# Front_panel.net
KiCad netlist of a schematic drawn in Altium Designer
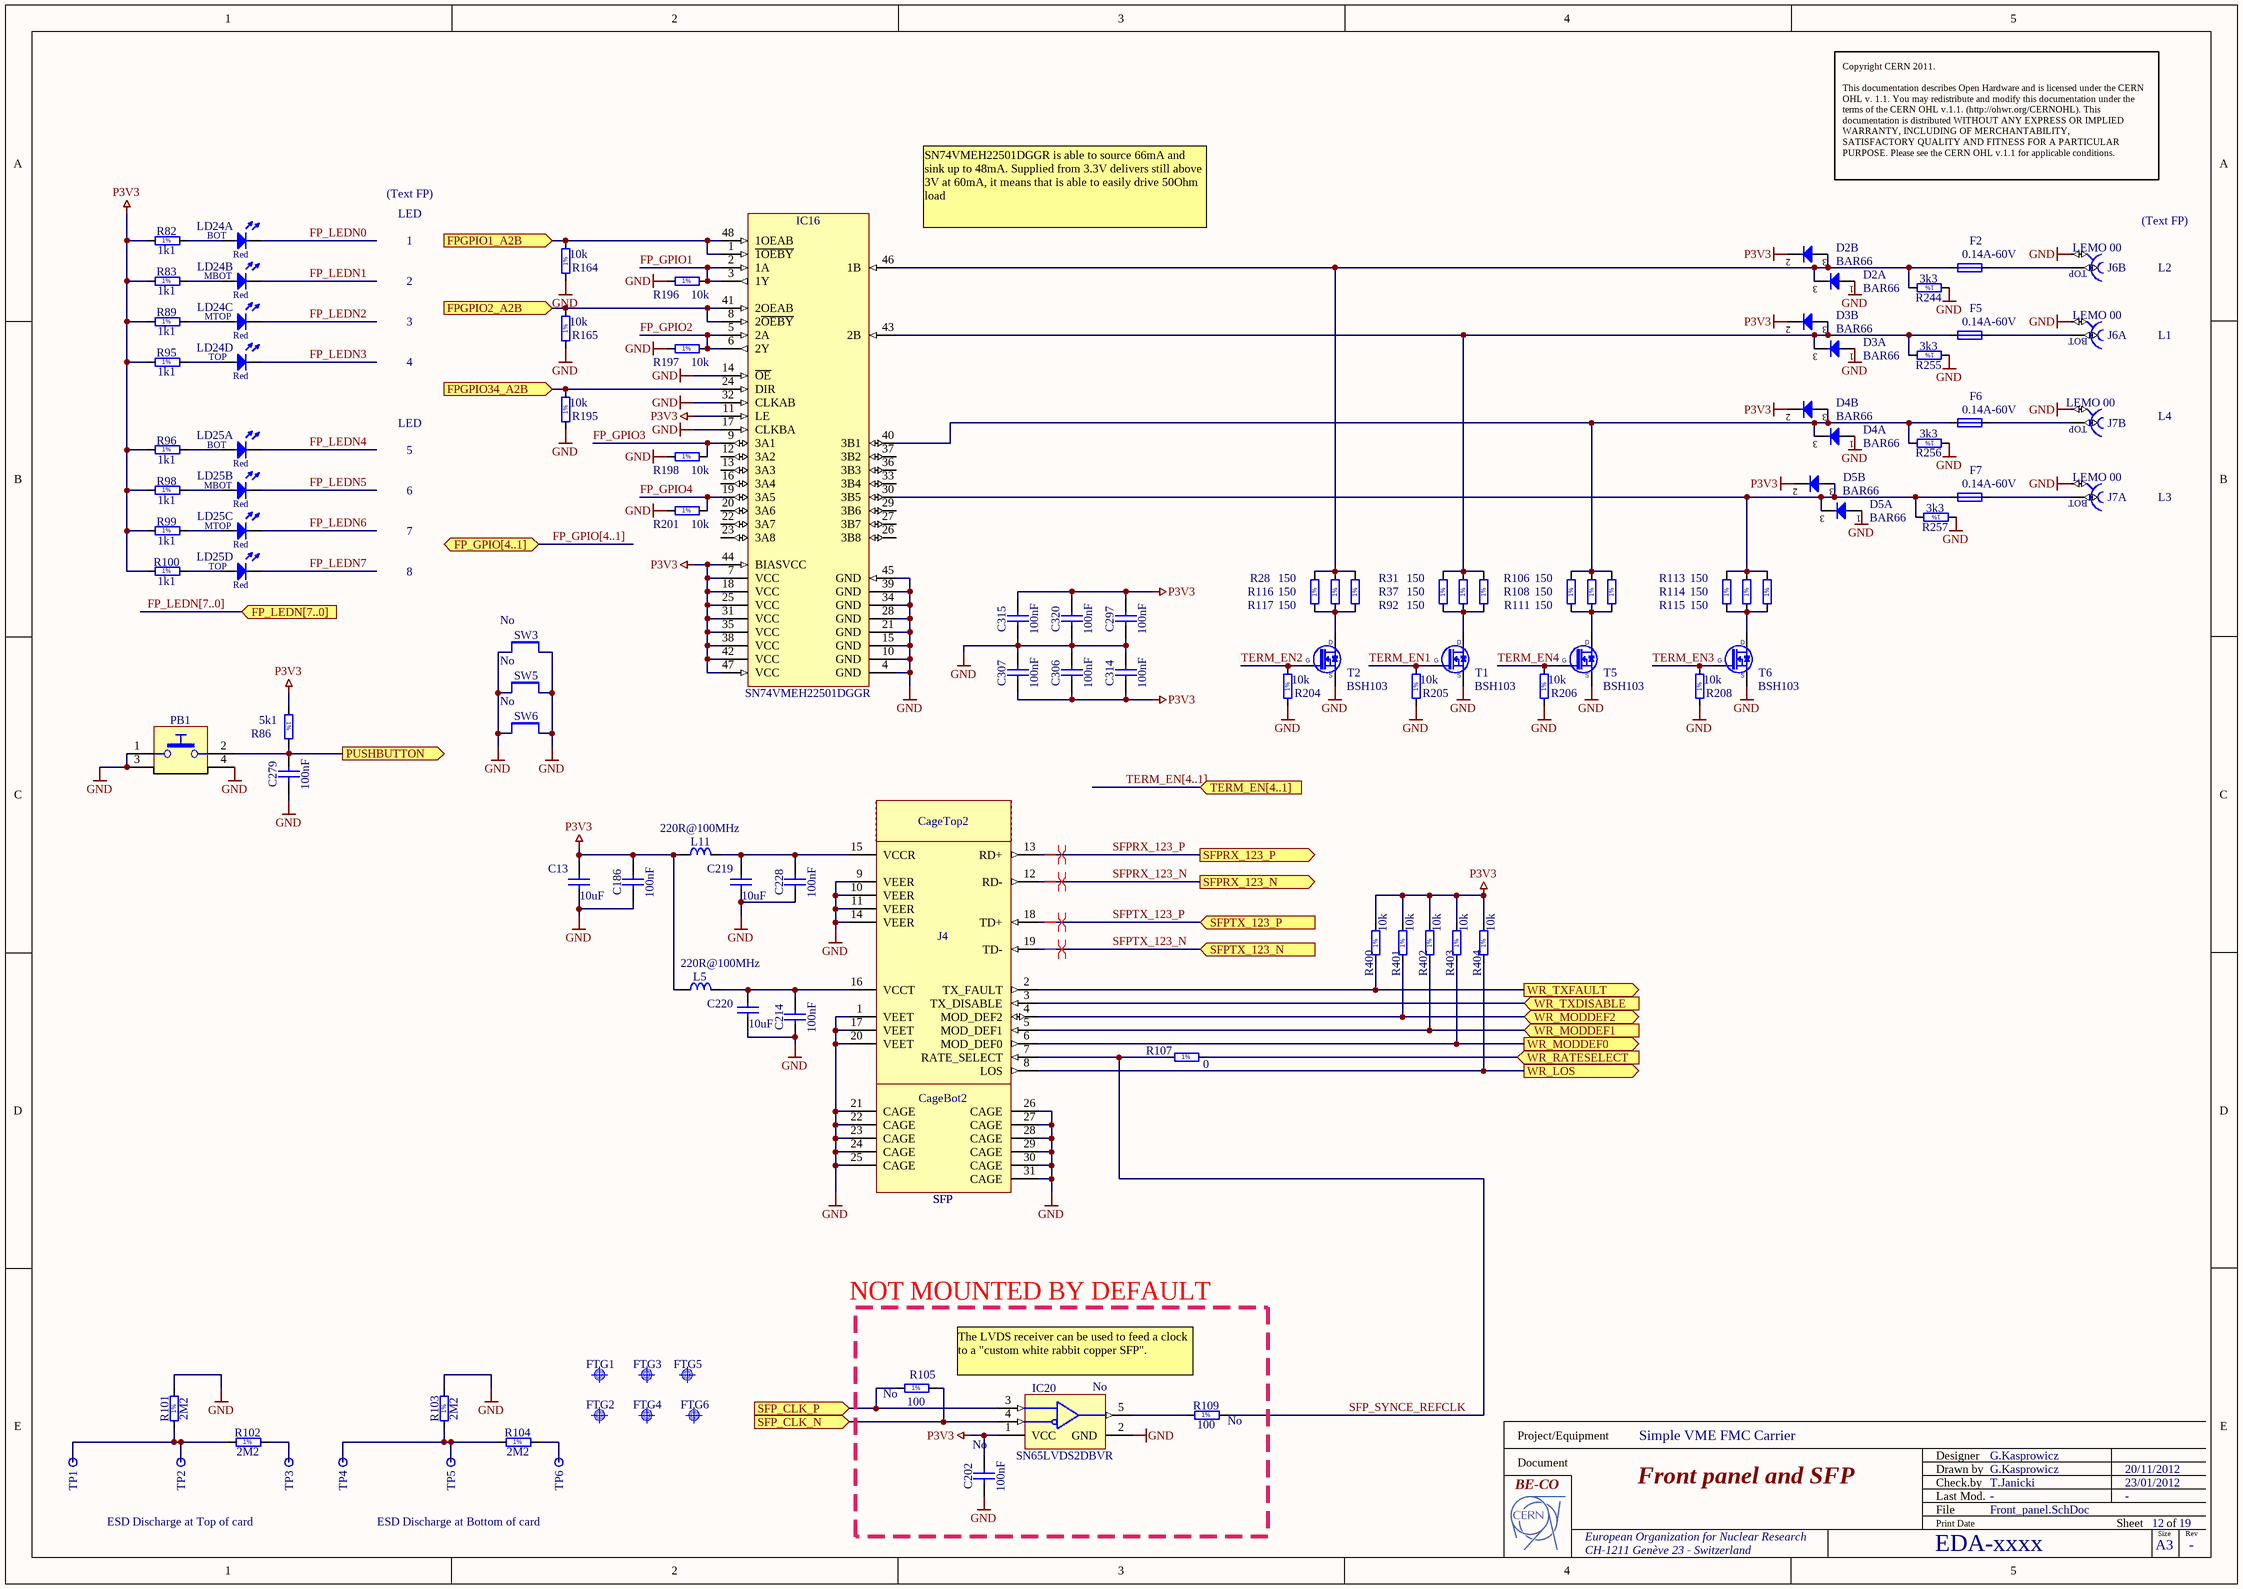
[diagram p0: Front_panel.SchDoc]

(export (version "E")
  (design (tool "Eeschema 10.0.6"))
  (components
    (comp (ref "C13")
      (value "10uF")
      (footprint "CAPC3225X270N")
      (description "Non-polarised capacitor")
      (fields (field (name "PART NUMBER") "CC1210_10UF_25V_10%_X7R") (field (name "VOLTAGE") "25V"))
      (libsource (lib "Capacitors") (part "Capacitor - non polarized"))
    )
    (comp (ref "C186")
      (value "100nF")
      (footprint "CAPC1005X55N")
      (description "Non-polarised capacitor")
      (fields (field (name "PART NUMBER") "CC0402_100NF_16V_10%_X7R") (field (name "VOLTAGE") "16V"))
      (libsource (lib "Capacitors") (part "Capacitor - non polarized"))
    )
    (comp (ref "C202")
      (value "100nF")
      (footprint "CAPC1005X55N")
      (description "Non-polarised capacitor")
      (fields
        (field (name "PART NUMBER") "CC0402_100NF_16V_10%_X7R")
        (field (name "VOLTAGE") "16V")
        (field (name "MOUNTED") "No")
      )
      (libsource (lib "Capacitors") (part "Capacitor - non polarized"))
    )
    (comp (ref "C214")
      (value "100nF")
      (footprint "CAPC1005X55N")
      (description "Non-polarised capacitor")
      (fields (field (name "PART NUMBER") "CC0402_100NF_16V_10%_X7R") (field (name "VOLTAGE") "16V"))
      (libsource (lib "Capacitors") (part "Capacitor - non polarized"))
    )
    (comp (ref "C219")
      (value "10uF")
      (footprint "CAPC3225X270N")
      (description "Non-polarised capacitor")
      (fields (field (name "PART NUMBER") "CC1210_10UF_25V_10%_X7R") (field (name "VOLTAGE") "25V"))
      (libsource (lib "Capacitors") (part "Capacitor - non polarized"))
    )
    (comp (ref "C220")
      (value "10uF")
      (footprint "CAPC3225X270N")
      (description "Non-polarised capacitor")
      (fields (field (name "PART NUMBER") "CC1210_10UF_25V_10%_X7R") (field (name "VOLTAGE") "25V"))
      (libsource (lib "Capacitors") (part "Capacitor - non polarized"))
    )
    (comp (ref "C228")
      (value "100nF")
      (footprint "CAPC1005X55N")
      (description "Non-polarised capacitor")
      (fields (field (name "PART NUMBER") "CC0402_100NF_16V_10%_X7R") (field (name "VOLTAGE") "16V"))
      (libsource (lib "Capacitors") (part "Capacitor - non polarized"))
    )
    (comp (ref "C279")
      (value "100nF")
      (footprint "CAPC1005X55N")
      (description "Non-polarised capacitor")
      (fields (field (name "PART NUMBER") "CC0402_100NF_16V_10%_X7R") (field (name "VOLTAGE") "16V"))
      (libsource (lib "Capacitors") (part "Capacitor - non polarized"))
    )
    (comp (ref "C297")
      (value "100nF")
      (footprint "CAPC1005X55N")
      (description "Non-polarised capacitor")
      (fields (field (name "PART NUMBER") "CC0402_100NF_16V_10%_X7R") (field (name "VOLTAGE") "16V"))
      (libsource (lib "Capacitors") (part "Capacitor - non polarized"))
    )
    (comp (ref "C306")
      (value "100nF")
      (footprint "CAPC1005X55N")
      (description "Non-polarised capacitor")
      (fields (field (name "PART NUMBER") "CC0402_100NF_16V_10%_X7R") (field (name "VOLTAGE") "16V"))
      (libsource (lib "Capacitors") (part "Capacitor - non polarized"))
    )
    (comp (ref "C307")
      (value "100nF")
      (footprint "CAPC1005X55N")
      (description "Non-polarised capacitor")
      (fields (field (name "PART NUMBER") "CC0402_100NF_16V_10%_X7R") (field (name "VOLTAGE") "16V"))
      (libsource (lib "Capacitors") (part "Capacitor - non polarized"))
    )
    (comp (ref "C314")
      (value "100nF")
      (footprint "CAPC1005X55N")
      (description "Non-polarised capacitor")
      (fields (field (name "PART NUMBER") "CC0402_100NF_16V_10%_X7R") (field (name "VOLTAGE") "16V"))
      (libsource (lib "Capacitors") (part "Capacitor - non polarized"))
    )
    (comp (ref "C315")
      (value "100nF")
      (footprint "CAPC1005X55N")
      (description "Non-polarised capacitor")
      (fields (field (name "PART NUMBER") "CC0402_100NF_16V_10%_X7R") (field (name "VOLTAGE") "16V"))
      (libsource (lib "Capacitors") (part "Capacitor - non polarized"))
    )
    (comp (ref "C320")
      (value "100nF")
      (footprint "CAPC1005X55N")
      (description "Non-polarised capacitor")
      (fields (field (name "PART NUMBER") "CC0402_100NF_16V_10%_X7R") (field (name "VOLTAGE") "16V"))
      (libsource (lib "Capacitors") (part "Capacitor - non polarized"))
    )
    (comp (ref "CageBot2")
      (value "SFP")
      (footprint "TYCO_6367034-1")
      (description "SFP  Cage Bottom (Small Form-factor Pluggable)")
      (fields (field (name "PART NUMBER") "TYCO_6367034-1") (field (name "MANUFACTURER") "TYCO ELECTRONICS"))
      (libsource (lib "Connectors") (part "SFPx1_Cage Bottom"))
    )
    (comp (ref "CageTop2")
      (value "SFP")
      (footprint "TYCO_6367035-1")
      (description "SFP  Cage Top (Small Form-factor Pluggable)")
      (fields (field (name "PART NUMBER") "TYCO_6367035-1") (field (name "MANUFACTURER") "TYCO ELECTRONICS"))
      (libsource (lib "Connectors") (part "SFPx1_Cage Top"))
    )
    (comp (ref "D2")
      (value "BAR66")
      (footprint "SOT95P240X110-3N")
      (description "Serial Diode")
      (fields (field (name "VOLTAGE") "150V") (field (name "POWER") "250mA"))
      (libsource (lib "ICs And Semiconductors") (part "Diode x2 A1C3_A3C2"))
    )
    (comp (ref "D3")
      (value "BAR66")
      (footprint "SOT95P240X110-3N")
      (description "Serial Diode")
      (fields (field (name "VOLTAGE") "150V") (field (name "POWER") "250mA"))
      (libsource (lib "ICs And Semiconductors") (part "Diode x2 A1C3_A3C2"))
    )
    (comp (ref "D4")
      (value "BAR66")
      (footprint "SOT95P240X110-3N")
      (description "Serial Diode")
      (fields (field (name "VOLTAGE") "150V") (field (name "POWER") "250mA"))
      (libsource (lib "ICs And Semiconductors") (part "Diode x2 A1C3_A3C2"))
    )
    (comp (ref "D5")
      (value "BAR66")
      (footprint "SOT95P240X110-3N")
      (description "Serial Diode")
      (fields (field (name "VOLTAGE") "150V") (field (name "POWER") "250mA"))
      (libsource (lib "ICs And Semiconductors") (part "Diode x2 A1C3_A3C2"))
    )
    (comp (ref "F2")
      (value "0.14A-60V")
      (footprint "FUSRC4632X90N")
      (description "Fuse")
      (fields
        (field (name "PART NUMBER") "FUSR1812_TYCO-miniSMD0114F")
        (field (name "MANUFACTURER") "TYCO ELECTRONICS")
      )
      (libsource (lib "Eletro-mechanical") (part "Fuse"))
    )
    (comp (ref "F5")
      (value "0.14A-60V")
      (footprint "FUSRC4632X90N")
      (description "Fuse")
      (fields
        (field (name "PART NUMBER") "FUSR1812_TYCO-miniSMD0114F")
        (field (name "MANUFACTURER") "TYCO ELECTRONICS")
      )
      (libsource (lib "Eletro-mechanical") (part "Fuse"))
    )
    (comp (ref "F6")
      (value "0.14A-60V")
      (footprint "FUSRC4632X90N")
      (description "Fuse")
      (fields
        (field (name "PART NUMBER") "FUSR1812_TYCO-miniSMD0114F")
        (field (name "MANUFACTURER") "TYCO ELECTRONICS")
      )
      (libsource (lib "Eletro-mechanical") (part "Fuse"))
    )
    (comp (ref "F7")
      (value "0.14A-60V")
      (footprint "FUSRC4632X90N")
      (description "Fuse")
      (fields
        (field (name "PART NUMBER") "FUSR1812_TYCO-miniSMD0114F")
        (field (name "MANUFACTURER") "TYCO ELECTRONICS")
      )
      (libsource (lib "Eletro-mechanical") (part "Fuse"))
    )
    (comp (ref "FTG1")
      (value "Use only in PCB")
      (footprint "FIDUCIAL_TOP_S100-200")
      (description "Fiducial Target")
      (fields (field (name "PART NUMBER") "FIDUCIAL_TARGET_S100-200"))
      (libsource (lib "Eletro-mechanical") (part "Fiducial Target"))
    )
    (comp (ref "FTG2")
      (value "Use only in PCB")
      (footprint "FIDUCIAL_TOP_S100-200")
      (description "Fiducial Target")
      (fields (field (name "PART NUMBER") "FIDUCIAL_TARGET_S100-200"))
      (libsource (lib "Eletro-mechanical") (part "Fiducial Target"))
    )
    (comp (ref "FTG3")
      (value "Use only in PCB")
      (footprint "FIDUCIAL_TOP_S100-200")
      (description "Fiducial Target")
      (fields (field (name "PART NUMBER") "FIDUCIAL_TARGET_S100-200"))
      (libsource (lib "Eletro-mechanical") (part "Fiducial Target"))
    )
    (comp (ref "FTG4")
      (value "Use only in PCB")
      (footprint "FIDUCIAL_TOP_S100-200")
      (description "Fiducial Target")
      (fields (field (name "PART NUMBER") "FIDUCIAL_TARGET_S100-200"))
      (libsource (lib "Eletro-mechanical") (part "Fiducial Target"))
    )
    (comp (ref "FTG5")
      (value "Use only in PCB")
      (footprint "FIDUCIAL_TOP_S100-200")
      (description "Fiducial Target")
      (fields (field (name "PART NUMBER") "FIDUCIAL_TARGET_S100-200"))
      (libsource (lib "Eletro-mechanical") (part "Fiducial Target"))
    )
    (comp (ref "FTG6")
      (value "Use only in PCB")
      (footprint "FIDUCIAL_TOP_S100-200")
      (description "Fiducial Target")
      (fields (field (name "PART NUMBER") "FIDUCIAL_TARGET_S100-200"))
      (libsource (lib "Eletro-mechanical") (part "Fiducial Target"))
    )
    (comp (ref "IC16")
      (value "SN74VMEH22501DGGR")
      (footprint "SOP50P810X120-48N")
      (description "8-Bit Universal Bus Transceiver and Two 1-Bit Bus Transceivers with 3-State Outputs")
      (fields (field (name "MANUFACTURER") "TEXAS INSTRUMENTS"))
      (libsource (lib "ICs And Semiconductors") (part "74VMEH22501"))
    )
    (comp (ref "IC20")
      (value "SN65LVDS2DBVR")
      (footprint "SOT95P280X145-5N")
      (description "High-Speed Differential Line Receiver")
      (fields (field (name "MANUFACTURER") "TEXAS INSTRUMENTS") (field (name "MOUNTED") "No"))
      (libsource (lib "ICs And Semiconductors") (part "SN65LVDS2DBVR"))
    )
    (comp (ref "J4")
      (value "SFP")
      (footprint "TYCO_1367073-1")
      (description "20 Position SFP  Connector (Small Form-factor Pluggable)")
      (fields (field (name "PART NUMBER") "TYCO_1367073-1") (field (name "MANUFACTURER") "TYCO ELECTRONICS"))
      (libsource (lib "Connectors") (part "SFPx1"))
    )
    (comp (ref "J6")
      (value "LEMO 00")
      (footprint "LEMO_EPY.00.250.NTNY")
      (description "Dual Female Coax 1-2 Common Shield 3")
      (fields (field (name "PART NUMBER") "LEMO_EPY.00.250.NTNY") (field (name "MANUFACTURER") "LEMO"))
      (libsource (lib "Connectors") (part "LEMO_EPY.00.250.NTN"))
    )
    (comp (ref "J7")
      (value "LEMO 00")
      (footprint "LEMO_EPY.00.250.NTNY")
      (description "Dual Female Coax 1-2 Common Shield 3")
      (fields (field (name "PART NUMBER") "LEMO_EPY.00.250.NTNY") (field (name "MANUFACTURER") "LEMO"))
      (libsource (lib "Connectors") (part "LEMO_EPY.00.250.NTN"))
    )
    (comp (ref "L5")
      (value "220R@100MHz")
      (footprint "INDC2012X105N")
      (description "Inductor")
      (fields (field (name "PART NUMBER") "IND0805_MURATA_BLM21PG221SN1D") (field (name "POWER") "2A"))
      (libsource (lib "Inductors & Transformers") (part "Inductor"))
    )
    (comp (ref "L11")
      (value "220R@100MHz")
      (footprint "INDC2012X105N")
      (description "Inductor")
      (fields (field (name "PART NUMBER") "IND0805_MURATA_BLM21PG221SN1D") (field (name "POWER") "2A"))
      (libsource (lib "Inductors & Transformers") (part "Inductor"))
    )
    (comp (ref "LD24")
      (value "HE Red")
      (footprint "LED_BIVAR_H485CHDL")
      (description "LED x4 Red 1C2A-BOT_3C4A_5C6A_7C8A-TOP")
      (fields (field (name "PART NUMBER") "LED_BIVAR_H485CHDL") (field (name "MANUFACTURER") "BIVAR"))
      (libsource (lib "ICs And Semiconductors") (part "LED x4 Red 1C2A-BOT_3C4A_5C6A_7C8A-TOP"))
    )
    (comp (ref "LD25")
      (value "HE Red")
      (footprint "LED_BIVAR_H485CHDL")
      (description "LED x4 Red 1C2A-BOT_3C4A_5C6A_7C8A-TOP")
      (fields (field (name "PART NUMBER") "LED_BIVAR_H485CHDL") (field (name "MANUFACTURER") "BIVAR"))
      (libsource (lib "ICs And Semiconductors") (part "LED x4 Red 1C2A-BOT_3C4A_5C6A_7C8A-TOP"))
    )
    (comp (ref "PB1")
      (value "Push Button")
      (footprint "PB_ALPS_SKHHLQA010")
      (description "Push-Button Switch SPDT")
      (fields (field (name "PART NUMBER") "PB_ALPS_SKHHLQA010") (field (name "MANUFACTURER") "ALPS"))
      (libsource (lib "Eletro-mechanical") (part "PB SPST 1NO-2NO 34CASE"))
    )
    (comp (ref "R28")
      (value "150")
      (footprint "RESC3216X65N")
      (description "Resistor - 1%")
      (fields (field (name "PART NUMBER") "R1206_150R_1%_0.25W_100PPM") (field (name "POWER") "0.25W"))
      (libsource (lib "Resistors") (part "Resistor - 1%"))
    )
    (comp (ref "R31")
      (value "150")
      (footprint "RESC3216X65N")
      (description "Resistor - 1%")
      (fields (field (name "PART NUMBER") "R1206_150R_1%_0.25W_100PPM") (field (name "POWER") "0.25W"))
      (libsource (lib "Resistors") (part "Resistor - 1%"))
    )
    (comp (ref "R37")
      (value "150")
      (footprint "RESC3216X65N")
      (description "Resistor - 1%")
      (fields (field (name "PART NUMBER") "R1206_150R_1%_0.25W_100PPM") (field (name "POWER") "0.25W"))
      (libsource (lib "Resistors") (part "Resistor - 1%"))
    )
    (comp (ref "R82")
      (value "1k1")
      (footprint "RESC1608X55N")
      (description "Resistor - 1%")
      (fields (field (name "PART NUMBER") "R0603_1K1_1%_0.1W_100PPM") (field (name "POWER") "0.1W"))
      (libsource (lib "Resistors") (part "Resistor - 1%"))
    )
    (comp (ref "R83")
      (value "1k1")
      (footprint "RESC1608X55N")
      (description "Resistor - 1%")
      (fields (field (name "PART NUMBER") "R0603_1K1_1%_0.1W_100PPM") (field (name "POWER") "0.1W"))
      (libsource (lib "Resistors") (part "Resistor - 1%"))
    )
    (comp (ref "R86")
      (value "5k1")
      (footprint "RESC1608X55N")
      (description "Resistor - 1%")
      (fields (field (name "PART NUMBER") "R0603_5K1_1%_0.1W_100PPM") (field (name "POWER") "0.1W"))
      (libsource (lib "Resistors") (part "Resistor - 1%"))
    )
    (comp (ref "R89")
      (value "1k1")
      (footprint "RESC1608X55N")
      (description "Resistor - 1%")
      (fields (field (name "PART NUMBER") "R0603_1K1_1%_0.1W_100PPM") (field (name "POWER") "0.1W"))
      (libsource (lib "Resistors") (part "Resistor - 1%"))
    )
    (comp (ref "R92")
      (value "150")
      (footprint "RESC3216X65N")
      (description "Resistor - 1%")
      (fields (field (name "PART NUMBER") "R1206_150R_1%_0.25W_100PPM") (field (name "POWER") "0.25W"))
      (libsource (lib "Resistors") (part "Resistor - 1%"))
    )
    (comp (ref "R95")
      (value "1k1")
      (footprint "RESC1608X55N")
      (description "Resistor - 1%")
      (fields (field (name "PART NUMBER") "R0603_1K1_1%_0.1W_100PPM") (field (name "POWER") "0.1W"))
      (libsource (lib "Resistors") (part "Resistor - 1%"))
    )
    (comp (ref "R96")
      (value "1k1")
      (footprint "RESC1608X55N")
      (description "Resistor - 1%")
      (fields (field (name "PART NUMBER") "R0603_1K1_1%_0.1W_100PPM") (field (name "POWER") "0.1W"))
      (libsource (lib "Resistors") (part "Resistor - 1%"))
    )
    (comp (ref "R98")
      (value "1k1")
      (footprint "RESC1608X55N")
      (description "Resistor - 1%")
      (fields (field (name "PART NUMBER") "R0603_1K1_1%_0.1W_100PPM") (field (name "POWER") "0.1W"))
      (libsource (lib "Resistors") (part "Resistor - 1%"))
    )
    (comp (ref "R99")
      (value "1k1")
      (footprint "RESC1608X55N")
      (description "Resistor - 1%")
      (fields (field (name "PART NUMBER") "R0603_1K1_1%_0.1W_100PPM") (field (name "POWER") "0.1W"))
      (libsource (lib "Resistors") (part "Resistor - 1%"))
    )
    (comp (ref "R100")
      (value "1k1")
      (footprint "RESC1608X55N")
      (description "Resistor - 1%")
      (fields (field (name "PART NUMBER") "R0603_1K1_1%_0.1W_100PPM") (field (name "POWER") "0.1W"))
      (libsource (lib "Resistors") (part "Resistor - 1%"))
    )
    (comp (ref "R101")
      (value "2M2")
      (footprint "RESC2012X60N")
      (description "Resistor - 1%")
      (fields (field (name "PART NUMBER") "R0805_2M2_1%_0.125W_100PPM") (field (name "POWER") "0.125W"))
      (libsource (lib "Resistors") (part "Resistor - 1%"))
    )
    (comp (ref "R102")
      (value "2M2")
      (footprint "RESC2012X60N")
      (description "Resistor - 1%")
      (fields (field (name "PART NUMBER") "R0805_2M2_1%_0.125W_100PPM") (field (name "POWER") "0.125W"))
      (libsource (lib "Resistors") (part "Resistor - 1%"))
    )
    (comp (ref "R103")
      (value "2M2")
      (footprint "RESC2012X60N")
      (description "Resistor - 1%")
      (fields (field (name "PART NUMBER") "R0805_2M2_1%_0.125W_100PPM") (field (name "POWER") "0.125W"))
      (libsource (lib "Resistors") (part "Resistor - 1%"))
    )
    (comp (ref "R104")
      (value "2M2")
      (footprint "RESC2012X60N")
      (description "Resistor - 1%")
      (fields (field (name "PART NUMBER") "R0805_2M2_1%_0.125W_100PPM") (field (name "POWER") "0.125W"))
      (libsource (lib "Resistors") (part "Resistor - 1%"))
    )
    (comp (ref "R105")
      (value "100")
      (footprint "RESC1608X55N")
      (description "Resistor - 1%")
      (fields
        (field (name "PART NUMBER") "R0603_100R_1%_0.1W_100PPM")
        (field (name "POWER") "0.1W")
        (field (name "MOUNTED") "No")
      )
      (libsource (lib "Resistors") (part "Resistor - 1%"))
    )
    (comp (ref "R106")
      (value "150")
      (footprint "RESC3216X65N")
      (description "Resistor - 1%")
      (fields (field (name "PART NUMBER") "R1206_150R_1%_0.25W_100PPM") (field (name "POWER") "0.25W"))
      (libsource (lib "Resistors") (part "Resistor - 1%"))
    )
    (comp (ref "R107")
      (value "0")
      (footprint "RESC1608X55N")
      (description "Resistor - 1%")
      (fields (field (name "PART NUMBER") "R0603_0R_JUMPER") (field (name "MANUFACTURER") "GENERIC"))
      (libsource (lib "Resistors") (part "Resistor - 1%"))
    )
    (comp (ref "R108")
      (value "150")
      (footprint "RESC3216X65N")
      (description "Resistor - 1%")
      (fields (field (name "PART NUMBER") "R1206_150R_1%_0.25W_100PPM") (field (name "POWER") "0.25W"))
      (libsource (lib "Resistors") (part "Resistor - 1%"))
    )
    (comp (ref "R109")
      (value "100")
      (footprint "RESC1608X55N")
      (description "Resistor - 1%")
      (fields
        (field (name "PART NUMBER") "R0603_100R_1%_0.1W_100PPM")
        (field (name "POWER") "0.1W")
        (field (name "MOUNTED") "No")
      )
      (libsource (lib "Resistors") (part "Resistor - 1%"))
    )
    (comp (ref "R111")
      (value "150")
      (footprint "RESC3216X65N")
      (description "Resistor - 1%")
      (fields (field (name "PART NUMBER") "R1206_150R_1%_0.25W_100PPM") (field (name "POWER") "0.25W"))
      (libsource (lib "Resistors") (part "Resistor - 1%"))
    )
    (comp (ref "R113")
      (value "150")
      (footprint "RESC3216X65N")
      (description "Resistor - 1%")
      (fields (field (name "PART NUMBER") "R1206_150R_1%_0.25W_100PPM") (field (name "POWER") "0.25W"))
      (libsource (lib "Resistors") (part "Resistor - 1%"))
    )
    (comp (ref "R114")
      (value "150")
      (footprint "RESC3216X65N")
      (description "Resistor - 1%")
      (fields (field (name "PART NUMBER") "R1206_150R_1%_0.25W_100PPM") (field (name "POWER") "0.25W"))
      (libsource (lib "Resistors") (part "Resistor - 1%"))
    )
    (comp (ref "R115")
      (value "150")
      (footprint "RESC3216X65N")
      (description "Resistor - 1%")
      (fields (field (name "PART NUMBER") "R1206_150R_1%_0.25W_100PPM") (field (name "POWER") "0.25W"))
      (libsource (lib "Resistors") (part "Resistor - 1%"))
    )
    (comp (ref "R116")
      (value "150")
      (footprint "RESC3216X65N")
      (description "Resistor - 1%")
      (fields (field (name "PART NUMBER") "R1206_150R_1%_0.25W_100PPM") (field (name "POWER") "0.25W"))
      (libsource (lib "Resistors") (part "Resistor - 1%"))
    )
    (comp (ref "R117")
      (value "150")
      (footprint "RESC3216X65N")
      (description "Resistor - 1%")
      (fields (field (name "PART NUMBER") "R1206_150R_1%_0.25W_100PPM") (field (name "POWER") "0.25W"))
      (libsource (lib "Resistors") (part "Resistor - 1%"))
    )
    (comp (ref "R164")
      (value "10k")
      (footprint "RESC1608X55N")
      (description "Resistor - 1%")
      (fields (field (name "PART NUMBER") "R0603_10K_1%_0.1W_100PPM") (field (name "POWER") "0.1W"))
      (libsource (lib "Resistors") (part "Resistor - 1%"))
    )
    (comp (ref "R165")
      (value "10k")
      (footprint "RESC1608X55N")
      (description "Resistor - 1%")
      (fields (field (name "PART NUMBER") "R0603_10K_1%_0.1W_100PPM") (field (name "POWER") "0.1W"))
      (libsource (lib "Resistors") (part "Resistor - 1%"))
    )
    (comp (ref "R195")
      (value "10k")
      (footprint "RESC1608X55N")
      (description "Resistor - 1%")
      (fields (field (name "PART NUMBER") "R0603_10K_1%_0.1W_100PPM") (field (name "POWER") "0.1W"))
      (libsource (lib "Resistors") (part "Resistor - 1%"))
    )
    (comp (ref "R196")
      (value "10k")
      (footprint "RESC1608X55N")
      (description "Resistor - 1%")
      (fields (field (name "PART NUMBER") "R0603_10K_1%_0.1W_100PPM") (field (name "POWER") "0.1W"))
      (libsource (lib "Resistors") (part "Resistor - 1%"))
    )
    (comp (ref "R197")
      (value "10k")
      (footprint "RESC1608X55N")
      (description "Resistor - 1%")
      (fields (field (name "PART NUMBER") "R0603_10K_1%_0.1W_100PPM") (field (name "POWER") "0.1W"))
      (libsource (lib "Resistors") (part "Resistor - 1%"))
    )
    (comp (ref "R198")
      (value "10k")
      (footprint "RESC1608X55N")
      (description "Resistor - 1%")
      (fields (field (name "PART NUMBER") "R0603_10K_1%_0.1W_100PPM") (field (name "POWER") "0.1W"))
      (libsource (lib "Resistors") (part "Resistor - 1%"))
    )
    (comp (ref "R201")
      (value "10k")
      (footprint "RESC1608X55N")
      (description "Resistor - 1%")
      (fields (field (name "PART NUMBER") "R0603_10K_1%_0.1W_100PPM") (field (name "POWER") "0.1W"))
      (libsource (lib "Resistors") (part "Resistor - 1%"))
    )
    (comp (ref "R204")
      (value "10k")
      (footprint "RESC1608X55N")
      (description "Resistor - 1%")
      (fields (field (name "PART NUMBER") "R0603_10K_1%_0.1W_100PPM") (field (name "POWER") "0.1W"))
      (libsource (lib "Resistors") (part "Resistor - 1%"))
    )
    (comp (ref "R205")
      (value "10k")
      (footprint "RESC1608X55N")
      (description "Resistor - 1%")
      (fields (field (name "PART NUMBER") "R0603_10K_1%_0.1W_100PPM") (field (name "POWER") "0.1W"))
      (libsource (lib "Resistors") (part "Resistor - 1%"))
    )
    (comp (ref "R206")
      (value "10k")
      (footprint "RESC1608X55N")
      (description "Resistor - 1%")
      (fields (field (name "PART NUMBER") "R0603_10K_1%_0.1W_100PPM") (field (name "POWER") "0.1W"))
      (libsource (lib "Resistors") (part "Resistor - 1%"))
    )
    (comp (ref "R208")
      (value "10k")
      (footprint "RESC1608X55N")
      (description "Resistor - 1%")
      (fields (field (name "PART NUMBER") "R0603_10K_1%_0.1W_100PPM") (field (name "POWER") "0.1W"))
      (libsource (lib "Resistors") (part "Resistor - 1%"))
    )
    (comp (ref "R244")
      (value "3k3")
      (footprint "RESC1608X55N")
      (description "Resistor - 1%")
      (fields (field (name "PART NUMBER") "R0603_3K3_1%_0.1W_100PPM") (field (name "POWER") "0.1W"))
      (libsource (lib "Resistors") (part "Resistor - 1%"))
    )
    (comp (ref "R255")
      (value "3k3")
      (footprint "RESC1608X55N")
      (description "Resistor - 1%")
      (fields (field (name "PART NUMBER") "R0603_3K3_1%_0.1W_100PPM") (field (name "POWER") "0.1W"))
      (libsource (lib "Resistors") (part "Resistor - 1%"))
    )
    (comp (ref "R256")
      (value "3k3")
      (footprint "RESC1608X55N")
      (description "Resistor - 1%")
      (fields (field (name "PART NUMBER") "R0603_3K3_1%_0.1W_100PPM") (field (name "POWER") "0.1W"))
      (libsource (lib "Resistors") (part "Resistor - 1%"))
    )
    (comp (ref "R257")
      (value "3k3")
      (footprint "RESC1608X55N")
      (description "Resistor - 1%")
      (fields (field (name "PART NUMBER") "R0603_3K3_1%_0.1W_100PPM") (field (name "POWER") "0.1W"))
      (libsource (lib "Resistors") (part "Resistor - 1%"))
    )
    (comp (ref "R400")
      (value "10k")
      (footprint "RESC1608X55N")
      (description "Resistor - 1%")
      (fields (field (name "PART NUMBER") "R0603_10K_1%_0.1W_100PPM") (field (name "POWER") "0.1W"))
      (libsource (lib "Resistors") (part "Resistor - 1%"))
    )
    (comp (ref "R401")
      (value "10k")
      (footprint "RESC1608X55N")
      (description "Resistor - 1%")
      (fields (field (name "PART NUMBER") "R0603_10K_1%_0.1W_100PPM") (field (name "POWER") "0.1W"))
      (libsource (lib "Resistors") (part "Resistor - 1%"))
    )
    (comp (ref "R402")
      (value "10k")
      (footprint "RESC1608X55N")
      (description "Resistor - 1%")
      (fields (field (name "PART NUMBER") "R0603_10K_1%_0.1W_100PPM") (field (name "POWER") "0.1W"))
      (libsource (lib "Resistors") (part "Resistor - 1%"))
    )
    (comp (ref "R403")
      (value "10k")
      (footprint "RESC1608X55N")
      (description "Resistor - 1%")
      (fields (field (name "PART NUMBER") "R0603_10K_1%_0.1W_100PPM") (field (name "POWER") "0.1W"))
      (libsource (lib "Resistors") (part "Resistor - 1%"))
    )
    (comp (ref "R404")
      (value "10k")
      (footprint "RESC1608X55N")
      (description "Resistor - 1%")
      (fields (field (name "PART NUMBER") "R0603_10K_1%_0.1W_100PPM") (field (name "POWER") "0.1W"))
      (libsource (lib "Resistors") (part "Resistor - 1%"))
    )
    (comp (ref "SW3")
      (value "Jumper Type2")
      (footprint "COMATEL_313.0004.0.00.500")
      (description "Jumper 2 pins")
      (fields
        (field (name "PART NUMBER") "COMATEL_313.0004.0.00.500")
        (field (name "MOUNTED") "No")
        (field (name "MANUFACTURER") "KONTEK COMATEL")
      )
      (libsource (lib "Connectors") (part "Jumper Type2"))
    )
    (comp (ref "SW5")
      (value "Jumper Type2")
      (footprint "COMATEL_313.0004.0.00.500")
      (description "Jumper 2 pins")
      (fields
        (field (name "PART NUMBER") "COMATEL_313.0004.0.00.500")
        (field (name "MOUNTED") "No")
        (field (name "MANUFACTURER") "KONTEK COMATEL")
      )
      (libsource (lib "Connectors") (part "Jumper Type2"))
    )
    (comp (ref "SW6")
      (value "Jumper Type2")
      (footprint "COMATEL_313.0004.0.00.500")
      (description "Jumper 2 pins")
      (fields
        (field (name "PART NUMBER") "COMATEL_313.0004.0.00.500")
        (field (name "MOUNTED") "No")
        (field (name "MANUFACTURER") "KONTEK COMATEL")
      )
      (libsource (lib "Connectors") (part "Jumper Type2"))
    )
    (comp (ref "T1")
      (value "BSH103")
      (footprint "SOT95P230X110-3N")
      (description "N-CHANNEL MOSFET WITH DIODE")
      (fields (field (name "MANUFACTURER") "NXP SEMICONDUCTORS"))
      (libsource (lib "ICs And Semiconductors") (part "N-MOSFET-D 1G 2S 3D"))
    )
    (comp (ref "T2")
      (value "BSH103")
      (footprint "SOT95P230X110-3N")
      (description "N-CHANNEL MOSFET WITH DIODE")
      (fields (field (name "MANUFACTURER") "NXP SEMICONDUCTORS"))
      (libsource (lib "ICs And Semiconductors") (part "N-MOSFET-D 1G 2S 3D"))
    )
    (comp (ref "T5")
      (value "BSH103")
      (footprint "SOT95P230X110-3N")
      (description "N-CHANNEL MOSFET WITH DIODE")
      (fields (field (name "MANUFACTURER") "NXP SEMICONDUCTORS"))
      (libsource (lib "ICs And Semiconductors") (part "N-MOSFET-D 1G 2S 3D"))
    )
    (comp (ref "T6")
      (value "BSH103")
      (footprint "SOT95P230X110-3N")
      (description "N-CHANNEL MOSFET WITH DIODE")
      (fields (field (name "MANUFACTURER") "NXP SEMICONDUCTORS"))
      (libsource (lib "ICs And Semiconductors") (part "N-MOSFET-D 1G 2S 3D"))
    )
    (comp (ref "TP1")
      (value "Test Point")
      (footprint "TPS127")
      (fields (field (name "PART NUMBER") "SMD_PAD_1.27X1.27MM"))
      (libsource (lib "Eletro-mechanical") (part "Test Point"))
    )
    (comp (ref "TP2")
      (value "Test Point")
      (footprint "TPS127")
      (fields (field (name "PART NUMBER") "SMD_PAD_1.27X1.27MM"))
      (libsource (lib "Eletro-mechanical") (part "Test Point"))
    )
    (comp (ref "TP3")
      (value "Test Point")
      (footprint "TPS127")
      (fields (field (name "PART NUMBER") "SMD_PAD_1.27X1.27MM"))
      (libsource (lib "Eletro-mechanical") (part "Test Point"))
    )
    (comp (ref "TP4")
      (value "Test Point")
      (footprint "TPS127")
      (fields (field (name "PART NUMBER") "SMD_PAD_1.27X1.27MM"))
      (libsource (lib "Eletro-mechanical") (part "Test Point"))
    )
    (comp (ref "TP5")
      (value "Test Point")
      (footprint "TPS127")
      (fields (field (name "PART NUMBER") "SMD_PAD_1.27X1.27MM"))
      (libsource (lib "Eletro-mechanical") (part "Test Point"))
    )
    (comp (ref "TP6")
      (value "Test Point")
      (footprint "TPS127")
      (fields (field (name "PART NUMBER") "SMD_PAD_1.27X1.27MM"))
      (libsource (lib "Eletro-mechanical") (part "Test Point"))
    )
  )
  (nets
    (net (code "1") (name "/FPGPIO1_A2B") (class "Default")
      (node (ref "IC16") (pin "1") (pinfunction "~{1OEBY}_1") (pintype "input"))
      (node (ref "IC16") (pin "48") (pinfunction "1OEAB_48") (pintype "input"))
      (node (ref "R164") (pin "2") (pinfunction "2_2") (pintype "passive"))
    )
    (net (code "2") (name "/FPGPIO2_A2B") (class "Default")
      (node (ref "IC16") (pin "41") (pinfunction "2OEAB_41") (pintype "input"))
      (node (ref "IC16") (pin "8") (pinfunction "2~{OEBY}_8") (pintype "input"))
      (node (ref "R165") (pin "2") (pinfunction "2_2") (pintype "passive"))
    )
    (net (code "3") (name "/FPGPIO34_A2B") (class "Default")
      (node (ref "IC16") (pin "24") (pinfunction "DIR_24") (pintype "input"))
      (node (ref "R195") (pin "2") (pinfunction "2_2") (pintype "passive"))
    )
    (net (code "4") (name "/FP_GPIO1") (class "Default")
      (node (ref "IC16") (pin "2") (pinfunction "1A_2") (pintype "input"))
      (node (ref "IC16") (pin "3") (pinfunction "1Y_3") (pintype "output"))
      (node (ref "R196") (pin "2") (pinfunction "2_2") (pintype "passive"))
    )
    (net (code "5") (name "/FP_GPIO2") (class "Default")
      (node (ref "IC16") (pin "5") (pinfunction "2A_5") (pintype "input"))
      (node (ref "IC16") (pin "6") (pinfunction "2Y_6") (pintype "output"))
      (node (ref "R197") (pin "2") (pinfunction "2_2") (pintype "passive"))
    )
    (net (code "6") (name "/FP_GPIO3") (class "Default")
      (node (ref "IC16") (pin "9") (pinfunction "3A1_9") (pintype "bidirectional"))
      (node (ref "R198") (pin "2") (pinfunction "2_2") (pintype "passive"))
    )
    (net (code "7") (name "/FP_GPIO4") (class "Default")
      (node (ref "IC16") (pin "19") (pinfunction "3A5_19") (pintype "bidirectional"))
      (node (ref "R201") (pin "2") (pinfunction "2_2") (pintype "passive"))
    )
    (net (code "9") (name "/FP_LEDN0") (class "Default")
      (node (ref "LD24") (pin "1") (pinfunction "C_1") (pintype "passive"))
    )
    (net (code "10") (name "/FP_LEDN1") (class "Default")
      (node (ref "LD24") (pin "3") (pinfunction "C_3") (pintype "passive"))
    )
    (net (code "11") (name "/FP_LEDN2") (class "Default")
      (node (ref "LD24") (pin "5") (pinfunction "C_5") (pintype "passive"))
    )
    (net (code "12") (name "/FP_LEDN3") (class "Default")
      (node (ref "LD24") (pin "7") (pinfunction "C_7") (pintype "passive"))
    )
    (net (code "13") (name "/FP_LEDN4") (class "Default")
      (node (ref "LD25") (pin "1") (pinfunction "C_1") (pintype "passive"))
    )
    (net (code "14") (name "/FP_LEDN5") (class "Default")
      (node (ref "LD25") (pin "3") (pinfunction "C_3") (pintype "passive"))
    )
    (net (code "15") (name "/FP_LEDN6") (class "Default")
      (node (ref "LD25") (pin "5") (pinfunction "C_5") (pintype "passive"))
    )
    (net (code "16") (name "/FP_LEDN7") (class "Default")
      (node (ref "LD25") (pin "7") (pinfunction "C_7") (pintype "passive"))
    )
    (net (code "18") (name "/PUSHBUTTON") (class "Default")
      (node (ref "C279") (pin "2") (pinfunction "2_2") (pintype "passive"))
      (node (ref "PB1") (pin "2") (pinfunction "2_2") (pintype "passive"))
      (node (ref "R86") (pin "2") (pinfunction "2_2") (pintype "passive"))
    )
    (net (code "19") (name "/SFPRX_123_N") (class "Default")
      (node (ref "J4") (pin "12") (pinfunction "RD-_12") (pintype "output"))
    )
    (net (code "20") (name "/SFPRX_123_P") (class "Default")
      (node (ref "J4") (pin "13") (pinfunction "RD+_13") (pintype "output"))
    )
    (net (code "21") (name "/SFPTX_123_N") (class "Default")
      (node (ref "J4") (pin "19") (pinfunction "TD-_19") (pintype "input"))
    )
    (net (code "22") (name "/SFPTX_123_P") (class "Default")
      (node (ref "J4") (pin "18") (pinfunction "TD+_18") (pintype "input"))
    )
    (net (code "23") (name "/SFP_CLK_N") (class "Default")
      (node (ref "IC20") (pin "4") (pinfunction "B_4") (pintype "input"))
      (node (ref "R105") (pin "2") (pinfunction "2_2") (pintype "passive"))
    )
    (net (code "24") (name "/SFP_CLK_P") (class "Default")
      (node (ref "IC20") (pin "3") (pinfunction "A_3") (pintype "input"))
      (node (ref "R105") (pin "1") (pinfunction "1_1") (pintype "passive"))
    )
    (net (code "25") (name "/SFP_SYNCE_REFCLK") (class "Default")
      (node (ref "J4") (pin "7") (pinfunction "RATE_SELECT_7") (pintype "input"))
      (node (ref "R107") (pin "1") (pinfunction "1_1") (pintype "passive"))
      (node (ref "R109") (pin "2") (pinfunction "2_2") (pintype "passive"))
    )
    (net (code "26") (name "/TERM_EN1") (class "Default")
      (node (ref "R205") (pin "2") (pinfunction "2_2") (pintype "passive"))
      (node (ref "T1") (pin "1") (pinfunction "G_1") (pintype "passive"))
    )
    (net (code "27") (name "/TERM_EN2") (class "Default")
      (node (ref "R204") (pin "2") (pinfunction "2_2") (pintype "passive"))
      (node (ref "T2") (pin "1") (pinfunction "G_1") (pintype "passive"))
    )
    (net (code "28") (name "/TERM_EN3") (class "Default")
      (node (ref "R208") (pin "2") (pinfunction "2_2") (pintype "passive"))
      (node (ref "T6") (pin "1") (pinfunction "G_1") (pintype "passive"))
    )
    (net (code "29") (name "/TERM_EN4") (class "Default")
      (node (ref "R206") (pin "2") (pinfunction "2_2") (pintype "passive"))
      (node (ref "T5") (pin "1") (pinfunction "G_1") (pintype "passive"))
    )
    (net (code "31") (name "/WR_LOS") (class "Default")
      (node (ref "J4") (pin "8") (pinfunction "LOS_8") (pintype "output"))
      (node (ref "R404") (pin "1") (pinfunction "1_1") (pintype "passive"))
    )
    (net (code "32") (name "/WR_MODDEF0") (class "Default")
      (node (ref "J4") (pin "6") (pinfunction "MOD_DEF0_6") (pintype "output"))
      (node (ref "R403") (pin "1") (pinfunction "1_1") (pintype "passive"))
    )
    (net (code "33") (name "/WR_MODDEF1") (class "Default")
      (node (ref "J4") (pin "5") (pinfunction "MOD_DEF1_5") (pintype "input"))
      (node (ref "R402") (pin "1") (pinfunction "1_1") (pintype "passive"))
    )
    (net (code "34") (name "/WR_MODDEF2") (class "Default")
      (node (ref "J4") (pin "4") (pinfunction "MOD_DEF2_4") (pintype "bidirectional"))
      (node (ref "R401") (pin "1") (pinfunction "1_1") (pintype "passive"))
    )
    (net (code "35") (name "/WR_RATESELECT") (class "Default")
      (node (ref "R107") (pin "2") (pinfunction "2_2") (pintype "passive"))
    )
    (net (code "36") (name "/WR_TXDISABLE") (class "Default")
      (node (ref "J4") (pin "3") (pinfunction "TX_DISABLE_3") (pintype "input"))
    )
    (net (code "37") (name "/WR_TXFAULT") (class "Default")
      (node (ref "J4") (pin "2") (pinfunction "TX_FAULT_2") (pintype "output"))
      (node (ref "R400") (pin "1") (pinfunction "1_1") (pintype "passive"))
    )
    (net (code "38") (name "GND") (class "Default")
      (node (ref "C13") (pin "2") (pinfunction "2_2") (pintype "passive"))
      (node (ref "C186") (pin "2") (pinfunction "2_2") (pintype "passive"))
      (node (ref "C202") (pin "1") (pinfunction "1_1") (pintype "passive"))
      (node (ref "C214") (pin "2") (pinfunction "2_2") (pintype "passive"))
      (node (ref "C219") (pin "2") (pinfunction "2_2") (pintype "passive"))
      (node (ref "C220") (pin "2") (pinfunction "2_2") (pintype "passive"))
      (node (ref "C228") (pin "2") (pinfunction "2_2") (pintype "passive"))
      (node (ref "C279") (pin "1") (pinfunction "1_1") (pintype "passive"))
      (node (ref "C297") (pin "1") (pinfunction "1_1") (pintype "passive"))
      (node (ref "C306") (pin "2") (pinfunction "2_2") (pintype "passive"))
      (node (ref "C307") (pin "2") (pinfunction "2_2") (pintype "passive"))
      (node (ref "C314") (pin "2") (pinfunction "2_2") (pintype "passive"))
      (node (ref "C315") (pin "1") (pinfunction "1_1") (pintype "passive"))
      (node (ref "C320") (pin "1") (pinfunction "1_1") (pintype "passive"))
      (node (ref "CageBot2") (pin "21") (pinfunction "CAGE_21") (pintype "power_in"))
      (node (ref "CageBot2") (pin "22") (pinfunction "CAGE_22") (pintype "power_in"))
      (node (ref "CageBot2") (pin "23") (pinfunction "CAGE_23") (pintype "power_in"))
      (node (ref "CageBot2") (pin "24") (pinfunction "CAGE_24") (pintype "power_in"))
      (node (ref "CageBot2") (pin "25") (pinfunction "CAGE_25") (pintype "power_in"))
      (node (ref "CageBot2") (pin "26") (pinfunction "CAGE_26") (pintype "power_in"))
      (node (ref "CageBot2") (pin "27") (pinfunction "CAGE_27") (pintype "power_in"))
      (node (ref "CageBot2") (pin "28") (pinfunction "CAGE_28") (pintype "power_in"))
      (node (ref "CageBot2") (pin "29") (pinfunction "CAGE_29") (pintype "power_in"))
      (node (ref "CageBot2") (pin "30") (pinfunction "CAGE_30") (pintype "power_in"))
      (node (ref "CageBot2") (pin "31") (pinfunction "CAGE_31") (pintype "power_in"))
      (node (ref "D2") (pin "1") (pinfunction "A_1") (pintype "passive"))
      (node (ref "D3") (pin "1") (pinfunction "A_1") (pintype "passive"))
      (node (ref "D4") (pin "1") (pinfunction "A_1") (pintype "passive"))
      (node (ref "D5") (pin "1") (pinfunction "A_1") (pintype "passive"))
      (node (ref "IC16") (pin "10") (pinfunction "GND_10") (pintype "power_in"))
      (node (ref "IC16") (pin "14") (pinfunction "~{OE}_14") (pintype "input"))
      (node (ref "IC16") (pin "15") (pinfunction "GND_15") (pintype "power_in"))
      (node (ref "IC16") (pin "17") (pinfunction "CLKBA_17") (pintype "input"))
      (node (ref "IC16") (pin "21") (pinfunction "GND_21") (pintype "power_in"))
      (node (ref "IC16") (pin "28") (pinfunction "GND_28") (pintype "power_in"))
      (node (ref "IC16") (pin "32") (pinfunction "CLKAB_32") (pintype "input"))
      (node (ref "IC16") (pin "34") (pinfunction "GND_34") (pintype "power_in"))
      (node (ref "IC16") (pin "39") (pinfunction "GND_39") (pintype "power_in"))
      (node (ref "IC16") (pin "4") (pinfunction "GND_4") (pintype "power_in"))
      (node (ref "IC16") (pin "45") (pinfunction "GND_45") (pintype "input"))
      (node (ref "IC20") (pin "2") (pinfunction "GND_2") (pintype "power_in"))
      (node (ref "J4") (pin "1") (pinfunction "VEET_1") (pintype "power_in"))
      (node (ref "J4") (pin "10") (pinfunction "VEER_10") (pintype "power_in"))
      (node (ref "J4") (pin "11") (pinfunction "VEER_11") (pintype "power_in"))
      (node (ref "J4") (pin "14") (pinfunction "VEER_14") (pintype "power_in"))
      (node (ref "J4") (pin "17") (pinfunction "VEET_17") (pintype "power_in"))
      (node (ref "J4") (pin "20") (pinfunction "VEET_20") (pintype "power_in"))
      (node (ref "J4") (pin "9") (pinfunction "VEER_9") (pintype "power_in"))
      (node (ref "J6") (pin "3") (pinfunction "3_3") (pintype "bidirectional"))
      (node (ref "J7") (pin "3") (pinfunction "3_3") (pintype "bidirectional"))
      (node (ref "PB1") (pin "1") (pinfunction "1_1") (pintype "passive"))
      (node (ref "PB1") (pin "3") (pinfunction "3_3") (pintype "passive"))
      (node (ref "PB1") (pin "4") (pinfunction "4_4") (pintype "passive"))
      (node (ref "R101") (pin "2") (pinfunction "2_2") (pintype "passive"))
      (node (ref "R103") (pin "2") (pinfunction "2_2") (pintype "passive"))
      (node (ref "R164") (pin "1") (pinfunction "1_1") (pintype "passive"))
      (node (ref "R165") (pin "1") (pinfunction "1_1") (pintype "passive"))
      (node (ref "R195") (pin "1") (pinfunction "1_1") (pintype "passive"))
      (node (ref "R196") (pin "1") (pinfunction "1_1") (pintype "passive"))
      (node (ref "R197") (pin "1") (pinfunction "1_1") (pintype "passive"))
      (node (ref "R198") (pin "1") (pinfunction "1_1") (pintype "passive"))
      (node (ref "R201") (pin "1") (pinfunction "1_1") (pintype "passive"))
      (node (ref "R204") (pin "1") (pinfunction "1_1") (pintype "passive"))
      (node (ref "R205") (pin "1") (pinfunction "1_1") (pintype "passive"))
      (node (ref "R206") (pin "1") (pinfunction "1_1") (pintype "passive"))
      (node (ref "R208") (pin "1") (pinfunction "1_1") (pintype "passive"))
      (node (ref "R244") (pin "1") (pinfunction "1_1") (pintype "passive"))
      (node (ref "R255") (pin "1") (pinfunction "1_1") (pintype "passive"))
      (node (ref "R256") (pin "1") (pinfunction "1_1") (pintype "passive"))
      (node (ref "R257") (pin "1") (pinfunction "1_1") (pintype "passive"))
      (node (ref "SW3") (pin "1") (pinfunction "1_1") (pintype "bidirectional"))
      (node (ref "SW3") (pin "2") (pinfunction "2_2") (pintype "bidirectional"))
      (node (ref "SW5") (pin "1") (pinfunction "1_1") (pintype "bidirectional"))
      (node (ref "SW5") (pin "2") (pinfunction "2_2") (pintype "bidirectional"))
      (node (ref "SW6") (pin "1") (pinfunction "1_1") (pintype "bidirectional"))
      (node (ref "SW6") (pin "2") (pinfunction "2_2") (pintype "bidirectional"))
      (node (ref "T1") (pin "2") (pinfunction "S_2") (pintype "passive"))
      (node (ref "T2") (pin "2") (pinfunction "S_2") (pintype "passive"))
      (node (ref "T5") (pin "2") (pinfunction "S_2") (pintype "passive"))
      (node (ref "T6") (pin "2") (pinfunction "S_2") (pintype "passive"))
    )
    (net (code "39") (name "Net-(D2A-COMAC)") (class "Default")
      (node (ref "D2") (pin "3") (pinfunction "COMAC_3") (pintype "passive"))
      (node (ref "F2") (pin "1") (pinfunction "1_1") (pintype "passive"))
      (node (ref "IC16") (pin "46") (pinfunction "1B_46") (pintype "input"))
      (node (ref "R116") (pin "2") (pinfunction "2_2") (pintype "passive"))
      (node (ref "R117") (pin "2") (pinfunction "2_2") (pintype "passive"))
      (node (ref "R244") (pin "2") (pinfunction "2_2") (pintype "passive"))
      (node (ref "R28") (pin "2") (pinfunction "2_2") (pintype "passive"))
    )
    (net (code "40") (name "Net-(D3A-COMAC)") (class "Default")
      (node (ref "D3") (pin "3") (pinfunction "COMAC_3") (pintype "passive"))
      (node (ref "F5") (pin "1") (pinfunction "1_1") (pintype "passive"))
      (node (ref "IC16") (pin "43") (pinfunction "2B_43") (pintype "input"))
      (node (ref "R255") (pin "2") (pinfunction "2_2") (pintype "passive"))
      (node (ref "R31") (pin "2") (pinfunction "2_2") (pintype "passive"))
      (node (ref "R37") (pin "2") (pinfunction "2_2") (pintype "passive"))
      (node (ref "R92") (pin "2") (pinfunction "2_2") (pintype "passive"))
    )
    (net (code "41") (name "Net-(D4A-COMAC)") (class "Default")
      (node (ref "D4") (pin "3") (pinfunction "COMAC_3") (pintype "passive"))
      (node (ref "F6") (pin "1") (pinfunction "1_1") (pintype "passive"))
      (node (ref "IC16") (pin "40") (pinfunction "3B1_40") (pintype "bidirectional"))
      (node (ref "R106") (pin "2") (pinfunction "2_2") (pintype "passive"))
      (node (ref "R108") (pin "2") (pinfunction "2_2") (pintype "passive"))
      (node (ref "R111") (pin "2") (pinfunction "2_2") (pintype "passive"))
      (node (ref "R256") (pin "2") (pinfunction "2_2") (pintype "passive"))
    )
    (net (code "42") (name "Net-(D5A-COMAC)") (class "Default")
      (node (ref "D5") (pin "3") (pinfunction "COMAC_3") (pintype "passive"))
      (node (ref "F7") (pin "1") (pinfunction "1_1") (pintype "passive"))
      (node (ref "IC16") (pin "30") (pinfunction "3B5_30") (pintype "bidirectional"))
      (node (ref "R113") (pin "2") (pinfunction "2_2") (pintype "passive"))
      (node (ref "R114") (pin "2") (pinfunction "2_2") (pintype "passive"))
      (node (ref "R115") (pin "2") (pinfunction "2_2") (pintype "passive"))
      (node (ref "R257") (pin "2") (pinfunction "2_2") (pintype "passive"))
    )
    (net (code "43") (name "Net-(F2-Pad2)") (class "Default")
      (node (ref "F2") (pin "2") (pinfunction "2_2") (pintype "passive"))
      (node (ref "J6") (pin "2") (pinfunction "2_2") (pintype "bidirectional"))
    )
    (net (code "44") (name "Net-(F5-Pad2)") (class "Default")
      (node (ref "F5") (pin "2") (pinfunction "2_2") (pintype "passive"))
      (node (ref "J6") (pin "1") (pinfunction "1_1") (pintype "bidirectional"))
    )
    (net (code "45") (name "Net-(F6-Pad2)") (class "Default")
      (node (ref "F6") (pin "2") (pinfunction "2_2") (pintype "passive"))
      (node (ref "J7") (pin "2") (pinfunction "2_2") (pintype "bidirectional"))
    )
    (net (code "46") (name "Net-(F7-Pad2)") (class "Default")
      (node (ref "F7") (pin "2") (pinfunction "2_2") (pintype "passive"))
      (node (ref "J7") (pin "1") (pinfunction "1_1") (pintype "bidirectional"))
    )
    (net (code "47") (name "Net-(IC20-R)") (class "Default")
      (node (ref "IC20") (pin "5") (pinfunction "R_5") (pintype "output"))
      (node (ref "R109") (pin "1") (pinfunction "1_1") (pintype "passive"))
    )
    (net (code "48") (name "Net-(J4-VCCR)") (class "Default")
      (node (ref "C219") (pin "1") (pinfunction "1_1") (pintype "passive"))
      (node (ref "C228") (pin "1") (pinfunction "1_1") (pintype "passive"))
      (node (ref "J4") (pin "15") (pinfunction "VCCR_15") (pintype "power_in"))
      (node (ref "L11") (pin "2") (pinfunction "2_2") (pintype "passive"))
    )
    (net (code "49") (name "Net-(J4-VCCT)") (class "Default")
      (node (ref "C214") (pin "1") (pinfunction "1_1") (pintype "passive"))
      (node (ref "C220") (pin "1") (pinfunction "1_1") (pintype "passive"))
      (node (ref "J4") (pin "16") (pinfunction "VCCT_16") (pintype "power_in"))
      (node (ref "L5") (pin "2") (pinfunction "2_2") (pintype "passive"))
    )
    (net (code "50") (name "Net-(LD24A-A)") (class "Default")
      (node (ref "LD24") (pin "2") (pinfunction "A_2") (pintype "passive"))
      (node (ref "R82") (pin "2") (pinfunction "2_2") (pintype "passive"))
    )
    (net (code "51") (name "Net-(LD24B-A)") (class "Default")
      (node (ref "LD24") (pin "4") (pinfunction "A_4") (pintype "passive"))
      (node (ref "R83") (pin "2") (pinfunction "2_2") (pintype "passive"))
    )
    (net (code "52") (name "Net-(LD24C-A)") (class "Default")
      (node (ref "LD24") (pin "6") (pinfunction "A_6") (pintype "passive"))
      (node (ref "R89") (pin "2") (pinfunction "2_2") (pintype "passive"))
    )
    (net (code "53") (name "Net-(LD24D-A)") (class "Default")
      (node (ref "LD24") (pin "8") (pinfunction "A_8") (pintype "passive"))
      (node (ref "R95") (pin "2") (pinfunction "2_2") (pintype "passive"))
    )
    (net (code "54") (name "Net-(LD25A-A)") (class "Default")
      (node (ref "LD25") (pin "2") (pinfunction "A_2") (pintype "passive"))
      (node (ref "R96") (pin "2") (pinfunction "2_2") (pintype "passive"))
    )
    (net (code "55") (name "Net-(LD25B-A)") (class "Default")
      (node (ref "LD25") (pin "4") (pinfunction "A_4") (pintype "passive"))
      (node (ref "R98") (pin "2") (pinfunction "2_2") (pintype "passive"))
    )
    (net (code "56") (name "Net-(LD25C-A)") (class "Default")
      (node (ref "LD25") (pin "6") (pinfunction "A_6") (pintype "passive"))
      (node (ref "R99") (pin "2") (pinfunction "2_2") (pintype "passive"))
    )
    (net (code "57") (name "Net-(LD25D-A)") (class "Default")
      (node (ref "LD25") (pin "8") (pinfunction "A_8") (pintype "passive"))
      (node (ref "R100") (pin "2") (pinfunction "2_2") (pintype "passive"))
    )
    (net (code "58") (name "Net-(R101-Pad1)") (class "Default")
      (node (ref "R101") (pin "1") (pinfunction "1_1") (pintype "passive"))
      (node (ref "R102") (pin "1") (pinfunction "1_1") (pintype "passive"))
      (node (ref "TP1") (pin "1") (pinfunction "1_1") (pintype "bidirectional"))
      (node (ref "TP2") (pin "1") (pinfunction "1_1") (pintype "bidirectional"))
    )
    (net (code "59") (name "Net-(R102-Pad2)") (class "Default")
      (node (ref "R102") (pin "2") (pinfunction "2_2") (pintype "passive"))
      (node (ref "TP3") (pin "1") (pinfunction "1_1") (pintype "bidirectional"))
    )
    (net (code "60") (name "Net-(R103-Pad1)") (class "Default")
      (node (ref "R103") (pin "1") (pinfunction "1_1") (pintype "passive"))
      (node (ref "R104") (pin "1") (pinfunction "1_1") (pintype "passive"))
      (node (ref "TP4") (pin "1") (pinfunction "1_1") (pintype "bidirectional"))
      (node (ref "TP5") (pin "1") (pinfunction "1_1") (pintype "bidirectional"))
    )
    (net (code "61") (name "Net-(R104-Pad2)") (class "Default")
      (node (ref "R104") (pin "2") (pinfunction "2_2") (pintype "passive"))
      (node (ref "TP6") (pin "1") (pinfunction "1_1") (pintype "bidirectional"))
    )
    (net (code "62") (name "Net-(T1-D)") (class "Default")
      (node (ref "R31") (pin "1") (pinfunction "1_1") (pintype "passive"))
      (node (ref "R37") (pin "1") (pinfunction "1_1") (pintype "passive"))
      (node (ref "R92") (pin "1") (pinfunction "1_1") (pintype "passive"))
      (node (ref "T1") (pin "3") (pinfunction "D_3") (pintype "passive"))
    )
    (net (code "63") (name "Net-(T2-D)") (class "Default")
      (node (ref "R116") (pin "1") (pinfunction "1_1") (pintype "passive"))
      (node (ref "R117") (pin "1") (pinfunction "1_1") (pintype "passive"))
      (node (ref "R28") (pin "1") (pinfunction "1_1") (pintype "passive"))
      (node (ref "T2") (pin "3") (pinfunction "D_3") (pintype "passive"))
    )
    (net (code "64") (name "Net-(T5-D)") (class "Default")
      (node (ref "R106") (pin "1") (pinfunction "1_1") (pintype "passive"))
      (node (ref "R108") (pin "1") (pinfunction "1_1") (pintype "passive"))
      (node (ref "R111") (pin "1") (pinfunction "1_1") (pintype "passive"))
      (node (ref "T5") (pin "3") (pinfunction "D_3") (pintype "passive"))
    )
    (net (code "65") (name "Net-(T6-D)") (class "Default")
      (node (ref "R113") (pin "1") (pinfunction "1_1") (pintype "passive"))
      (node (ref "R114") (pin "1") (pinfunction "1_1") (pintype "passive"))
      (node (ref "R115") (pin "1") (pinfunction "1_1") (pintype "passive"))
      (node (ref "T6") (pin "3") (pinfunction "D_3") (pintype "passive"))
    )
    (net (code "66") (name "P3V3") (class "Default")
      (node (ref "C13") (pin "1") (pinfunction "1_1") (pintype "passive"))
      (node (ref "C186") (pin "1") (pinfunction "1_1") (pintype "passive"))
      (node (ref "C202") (pin "2") (pinfunction "2_2") (pintype "passive"))
      (node (ref "C297") (pin "2") (pinfunction "2_2") (pintype "passive"))
      (node (ref "C306") (pin "1") (pinfunction "1_1") (pintype "passive"))
      (node (ref "C307") (pin "1") (pinfunction "1_1") (pintype "passive"))
      (node (ref "C314") (pin "1") (pinfunction "1_1") (pintype "passive"))
      (node (ref "C315") (pin "2") (pinfunction "2_2") (pintype "passive"))
      (node (ref "C320") (pin "2") (pinfunction "2_2") (pintype "passive"))
      (node (ref "D2") (pin "2") (pinfunction "C_2") (pintype "passive"))
      (node (ref "D3") (pin "2") (pinfunction "C_2") (pintype "passive"))
      (node (ref "D4") (pin "2") (pinfunction "C_2") (pintype "passive"))
      (node (ref "D5") (pin "2") (pinfunction "C_2") (pintype "passive"))
      (node (ref "IC16") (pin "11") (pinfunction "LE_11") (pintype "input"))
      (node (ref "IC16") (pin "18") (pinfunction "VCC_18") (pintype "power_in"))
      (node (ref "IC16") (pin "25") (pinfunction "VCC_25") (pintype "power_in"))
      (node (ref "IC16") (pin "31") (pinfunction "VCC_31") (pintype "power_in"))
      (node (ref "IC16") (pin "35") (pinfunction "VCC_35") (pintype "power_in"))
      (node (ref "IC16") (pin "38") (pinfunction "VCC_38") (pintype "power_in"))
      (node (ref "IC16") (pin "42") (pinfunction "VCC_42") (pintype "power_in"))
      (node (ref "IC16") (pin "44") (pinfunction "BIASVCC_44") (pintype "input"))
      (node (ref "IC16") (pin "47") (pinfunction "VCC_47") (pintype "input"))
      (node (ref "IC16") (pin "7") (pinfunction "VCC_7") (pintype "power_in"))
      (node (ref "IC20") (pin "1") (pinfunction "VCC_1") (pintype "power_in"))
      (node (ref "L11") (pin "1") (pinfunction "1_1") (pintype "passive"))
      (node (ref "L5") (pin "1") (pinfunction "1_1") (pintype "passive"))
      (node (ref "R100") (pin "1") (pinfunction "1_1") (pintype "passive"))
      (node (ref "R400") (pin "2") (pinfunction "2_2") (pintype "passive"))
      (node (ref "R401") (pin "2") (pinfunction "2_2") (pintype "passive"))
      (node (ref "R402") (pin "2") (pinfunction "2_2") (pintype "passive"))
      (node (ref "R403") (pin "2") (pinfunction "2_2") (pintype "passive"))
      (node (ref "R404") (pin "2") (pinfunction "2_2") (pintype "passive"))
      (node (ref "R82") (pin "1") (pinfunction "1_1") (pintype "passive"))
      (node (ref "R83") (pin "1") (pinfunction "1_1") (pintype "passive"))
      (node (ref "R86") (pin "1") (pinfunction "1_1") (pintype "passive"))
      (node (ref "R89") (pin "1") (pinfunction "1_1") (pintype "passive"))
      (node (ref "R95") (pin "1") (pinfunction "1_1") (pintype "passive"))
      (node (ref "R96") (pin "1") (pinfunction "1_1") (pintype "passive"))
      (node (ref "R98") (pin "1") (pinfunction "1_1") (pintype "passive"))
      (node (ref "R99") (pin "1") (pinfunction "1_1") (pintype "passive"))
    )
    (net (code "67") (name "unconnected-(IC16-3A2-Pad12)") (class "Default")
      (node (ref "IC16") (pin "12") (pinfunction "3A2_12") (pintype "bidirectional"))
    )
    (net (code "68") (name "unconnected-(IC16-3A3-Pad13)") (class "Default")
      (node (ref "IC16") (pin "13") (pinfunction "3A3_13") (pintype "bidirectional"))
    )
    (net (code "69") (name "unconnected-(IC16-3A4-Pad16)") (class "Default")
      (node (ref "IC16") (pin "16") (pinfunction "3A4_16") (pintype "bidirectional"))
    )
    (net (code "70") (name "unconnected-(IC16-3A6-Pad20)") (class "Default")
      (node (ref "IC16") (pin "20") (pinfunction "3A6_20") (pintype "bidirectional"))
    )
    (net (code "71") (name "unconnected-(IC16-3A7-Pad22)") (class "Default")
      (node (ref "IC16") (pin "22") (pinfunction "3A7_22") (pintype "bidirectional"))
    )
    (net (code "72") (name "unconnected-(IC16-3A8-Pad23)") (class "Default")
      (node (ref "IC16") (pin "23") (pinfunction "3A8_23") (pintype "bidirectional"))
    )
    (net (code "73") (name "unconnected-(IC16-3B2-Pad37)") (class "Default")
      (node (ref "IC16") (pin "37") (pinfunction "3B2_37") (pintype "bidirectional"))
    )
    (net (code "74") (name "unconnected-(IC16-3B3-Pad36)") (class "Default")
      (node (ref "IC16") (pin "36") (pinfunction "3B3_36") (pintype "bidirectional"))
    )
    (net (code "75") (name "unconnected-(IC16-3B4-Pad33)") (class "Default")
      (node (ref "IC16") (pin "33") (pinfunction "3B4_33") (pintype "bidirectional"))
    )
    (net (code "76") (name "unconnected-(IC16-3B6-Pad29)") (class "Default")
      (node (ref "IC16") (pin "29") (pinfunction "3B6_29") (pintype "bidirectional"))
    )
    (net (code "77") (name "unconnected-(IC16-3B7-Pad27)") (class "Default")
      (node (ref "IC16") (pin "27") (pinfunction "3B7_27") (pintype "bidirectional"))
    )
    (net (code "78") (name "unconnected-(IC16-3B8-Pad26)") (class "Default")
      (node (ref "IC16") (pin "26") (pinfunction "3B8_26") (pintype "bidirectional"))
    )
  )
)
